# Simulador_Sensor_Hall.net
KiCad netlist of a schematic drawn in EAGLE
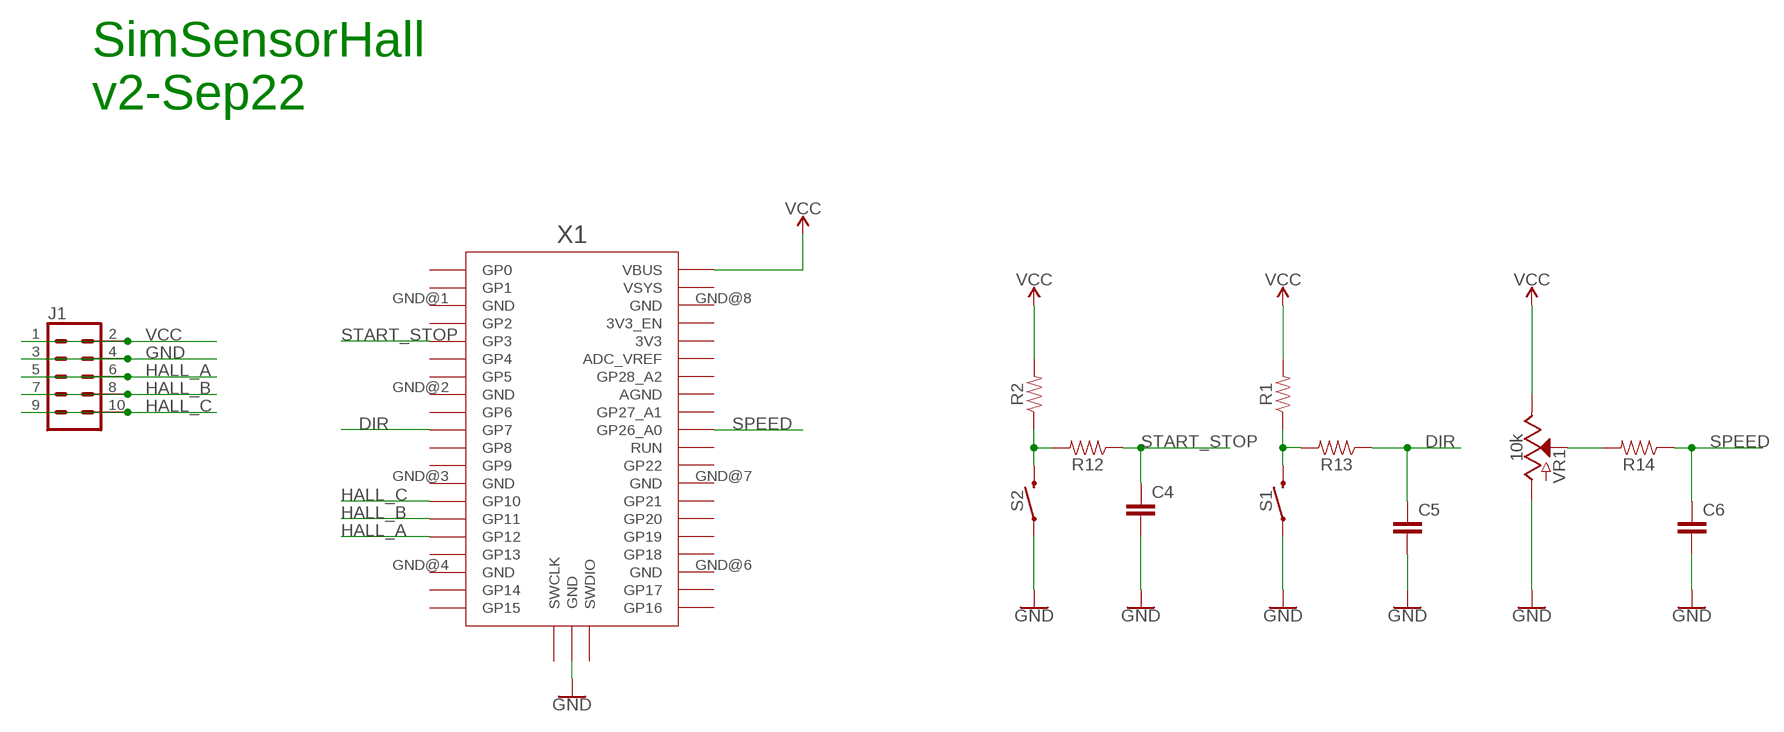
[diagram p0: schematic, sheet 1]

(export (version "E")
  (design (tool "Eeschema 10.0.6"))
  (components
    (comp (ref "C4")
      (value "C-EUC0805K")
      (footprint "eagle-import:C0805K")
      (libsource (lib "eagle-import") (part "C-EUC0805K"))
    )
    (comp (ref "C5")
      (value "C-EUC0805K")
      (footprint "eagle-import:C0805K")
      (libsource (lib "eagle-import") (part "C-EUC0805K"))
    )
    (comp (ref "C6")
      (value "C-EUC0805K")
      (footprint "eagle-import:C0805K")
      (libsource (lib "eagle-import") (part "C-EUC0805K"))
    )
    (comp (ref "J1")
      (value "CONN_05X2PTH")
      (footprint "eagle-import:2X5")
      (libsource (lib "eagle-import") (part "CONN_05X2PTH"))
    )
    (comp (ref "R1")
      (value "RESISTOR0805")
      (footprint "eagle-import:0805")
      (libsource (lib "eagle-import") (part "RESISTOR0805"))
    )
    (comp (ref "R2")
      (value "RESISTOR0805")
      (footprint "eagle-import:0805")
      (libsource (lib "eagle-import") (part "RESISTOR0805"))
    )
    (comp (ref "R12")
      (value "RESISTOR0805")
      (footprint "eagle-import:0805")
      (libsource (lib "eagle-import") (part "RESISTOR0805"))
    )
    (comp (ref "R13")
      (value "RESISTOR0805")
      (footprint "eagle-import:0805")
      (libsource (lib "eagle-import") (part "RESISTOR0805"))
    )
    (comp (ref "R14")
      (value "RESISTOR0805")
      (footprint "eagle-import:0805")
      (libsource (lib "eagle-import") (part "RESISTOR0805"))
    )
    (comp (ref "S1")
      (value "MOMENTARY-SWITCH-SPST-SMD-6.2MM-TALL")
      (footprint "eagle-import:TACTILE_SWITCH_SMD_6.2MM_TALL")
      (libsource (lib "eagle-import") (part "MOMENTARY-SWITCH-SPST-SMD-6.2MM-TALL"))
    )
    (comp (ref "S2")
      (value "MOMENTARY-SWITCH-SPST-SMD-6.2MM-TALL")
      (footprint "eagle-import:TACTILE_SWITCH_SMD_6.2MM_TALL")
      (libsource (lib "eagle-import") (part "MOMENTARY-SWITCH-SPST-SMD-6.2MM-TALL"))
    )
    (comp (ref "VR1")
      (value "10k")
      (footprint "eagle-import:POT-PTH-ALPS")
      (libsource (lib "eagle-import") (part "POTENTIOMETER-PTH-9MM-1/20W-20%"))
    )
    (comp (ref "X1")
      (value "RPI_PICO_IG-TH")
      (footprint "eagle-import:RPI_PICO_TH")
      (libsource (lib "eagle-import") (part "RPI_PICO_IG-TH"))
    )
  )
  (nets
    (net (code "1") (name "/DIR") (class "Default")
      (node (ref "C5") (pin "1") (pinfunction "1_1") (pintype "passive"))
      (node (ref "R13") (pin "1") (pinfunction "1_1") (pintype "passive"))
      (node (ref "X1") (pin "GP7") (pinfunction "GP7_GP7") (pintype "bidirectional"))
    )
    (net (code "2") (name "/HALL_A") (class "Default")
      (node (ref "J1") (pin "5") (pinfunction "5_5") (pintype "passive"))
      (node (ref "J1") (pin "6") (pinfunction "6_6") (pintype "passive"))
      (node (ref "X1") (pin "GP12") (pinfunction "GP12_GP12") (pintype "bidirectional"))
    )
    (net (code "3") (name "/HALL_B") (class "Default")
      (node (ref "J1") (pin "7") (pinfunction "7_7") (pintype "passive"))
      (node (ref "J1") (pin "8") (pinfunction "8_8") (pintype "passive"))
      (node (ref "X1") (pin "GP11") (pinfunction "GP11_GP11") (pintype "bidirectional"))
    )
    (net (code "4") (name "/HALL_C") (class "Default")
      (node (ref "J1") (pin "10") (pinfunction "10_10") (pintype "passive"))
      (node (ref "J1") (pin "9") (pinfunction "9_9") (pintype "passive"))
      (node (ref "X1") (pin "GP10") (pinfunction "GP10_GP10") (pintype "bidirectional"))
    )
    (net (code "5") (name "/SPEED") (class "Default")
      (node (ref "C6") (pin "1") (pinfunction "1_1") (pintype "passive"))
      (node (ref "R14") (pin "1") (pinfunction "1_1") (pintype "passive"))
      (node (ref "X1") (pin "GP26_A0") (pinfunction "GP26_A0_GP26_A0") (pintype "bidirectional"))
    )
    (net (code "6") (name "/START_STOP") (class "Default")
      (node (ref "C4") (pin "1") (pinfunction "1_1") (pintype "passive"))
      (node (ref "R12") (pin "1") (pinfunction "1_1") (pintype "passive"))
      (node (ref "X1") (pin "GP3") (pinfunction "GP3_GP3") (pintype "bidirectional"))
    )
    (net (code "7") (name "GND") (class "Default")
      (node (ref "C4") (pin "2") (pinfunction "2_2") (pintype "passive"))
      (node (ref "C5") (pin "2") (pinfunction "2_2") (pintype "passive"))
      (node (ref "C6") (pin "2") (pinfunction "2_2") (pintype "passive"))
      (node (ref "J1") (pin "3") (pinfunction "3_3") (pintype "passive"))
      (node (ref "J1") (pin "4") (pinfunction "4_4") (pintype "passive"))
      (node (ref "S1") (pin "A2") (pinfunction "1_A2") (pintype "passive"))
      (node (ref "S2") (pin "A2") (pinfunction "1_A2") (pintype "passive"))
      (node (ref "VR1") (pin "P$3") (pinfunction "A_P$3") (pintype "passive"))
      (node (ref "X1") (pin "GND@5") (pinfunction "GND_GND@5") (pintype "bidirectional"))
    )
    (net (code "8") (name "Net-(S1-2)") (class "Default")
      (node (ref "R1") (pin "1") (pinfunction "1_1") (pintype "passive"))
      (node (ref "R13") (pin "2") (pinfunction "2_2") (pintype "passive"))
      (node (ref "S1") (pin "B2") (pinfunction "2_B2") (pintype "passive"))
    )
    (net (code "9") (name "Net-(S2-2)") (class "Default")
      (node (ref "R12") (pin "2") (pinfunction "2_2") (pintype "passive"))
      (node (ref "R2") (pin "1") (pinfunction "1_1") (pintype "passive"))
      (node (ref "S2") (pin "B2") (pinfunction "2_B2") (pintype "passive"))
    )
    (net (code "10") (name "Net-(VR1-S)") (class "Default")
      (node (ref "R14") (pin "2") (pinfunction "2_2") (pintype "passive"))
      (node (ref "VR1") (pin "P$2") (pinfunction "S_P$2") (pintype "passive"))
    )
    (net (code "11") (name "VCC") (class "Default")
      (node (ref "J1") (pin "1") (pinfunction "1_1") (pintype "passive"))
      (node (ref "J1") (pin "2") (pinfunction "2_2") (pintype "passive"))
      (node (ref "R1") (pin "2") (pinfunction "2_2") (pintype "passive"))
      (node (ref "R2") (pin "2") (pinfunction "2_2") (pintype "passive"))
      (node (ref "VR1") (pin "P$1") (pinfunction "E_P$1") (pintype "passive"))
      (node (ref "X1") (pin "VBUS") (pinfunction "VBUS_VBUS") (pintype "bidirectional"))
    )
    (net (code "12") (name "unconnected-(X1-GND-PadGND@1)") (class "Default")
      (node (ref "X1") (pin "GND@1") (pinfunction "GND_GND@1") (pintype "bidirectional"))
    )
    (net (code "13") (name "unconnected-(X1-GND-PadGND@2)") (class "Default")
      (node (ref "X1") (pin "GND@2") (pinfunction "GND_GND@2") (pintype "bidirectional"))
    )
    (net (code "14") (name "unconnected-(X1-GND-PadGND@3)") (class "Default")
      (node (ref "X1") (pin "GND@3") (pinfunction "GND_GND@3") (pintype "bidirectional"))
    )
    (net (code "15") (name "unconnected-(X1-GND-PadGND@4)") (class "Default")
      (node (ref "X1") (pin "GND@4") (pinfunction "GND_GND@4") (pintype "bidirectional"))
    )
    (net (code "16") (name "unconnected-(X1-GND-PadGND@6)") (class "Default")
      (node (ref "X1") (pin "GND@6") (pinfunction "GND_GND@6") (pintype "bidirectional"))
    )
    (net (code "17") (name "unconnected-(X1-GND-PadGND@7)") (class "Default")
      (node (ref "X1") (pin "GND@7") (pinfunction "GND_GND@7") (pintype "bidirectional"))
    )
    (net (code "18") (name "unconnected-(X1-GND-PadGND@8)") (class "Default")
      (node (ref "X1") (pin "GND@8") (pinfunction "GND_GND@8") (pintype "bidirectional"))
    )
    (net (code "19") (name "unconnected-(X1-Pad3V3)") (class "Default")
      (node (ref "X1") (pin "3V3") (pinfunction "3V3_3V3") (pintype "bidirectional"))
    )
    (net (code "20") (name "unconnected-(X1-Pad3V3_EN)") (class "Default")
      (node (ref "X1") (pin "3V3_EN") (pinfunction "3V3_EN_3V3_EN") (pintype "bidirectional"))
    )
    (net (code "21") (name "unconnected-(X1-PadADC_VREF)") (class "Default")
      (node (ref "X1") (pin "ADC_VREF") (pinfunction "ADC_VREF_ADC_VREF") (pintype "bidirectional"))
    )
    (net (code "22") (name "unconnected-(X1-PadAGND)") (class "Default")
      (node (ref "X1") (pin "AGND") (pinfunction "AGND_AGND") (pintype "bidirectional"))
    )
    (net (code "23") (name "unconnected-(X1-PadGP0)") (class "Default")
      (node (ref "X1") (pin "GP0") (pinfunction "GP0_GP0") (pintype "bidirectional"))
    )
    (net (code "24") (name "unconnected-(X1-PadGP1)") (class "Default")
      (node (ref "X1") (pin "GP1") (pinfunction "GP1_GP1") (pintype "bidirectional"))
    )
    (net (code "25") (name "unconnected-(X1-PadGP2)") (class "Default")
      (node (ref "X1") (pin "GP2") (pinfunction "GP2_GP2") (pintype "bidirectional"))
    )
    (net (code "26") (name "unconnected-(X1-PadGP4)") (class "Default")
      (node (ref "X1") (pin "GP4") (pinfunction "GP4_GP4") (pintype "bidirectional"))
    )
    (net (code "27") (name "unconnected-(X1-PadGP5)") (class "Default")
      (node (ref "X1") (pin "GP5") (pinfunction "GP5_GP5") (pintype "bidirectional"))
    )
    (net (code "28") (name "unconnected-(X1-PadGP6)") (class "Default")
      (node (ref "X1") (pin "GP6") (pinfunction "GP6_GP6") (pintype "bidirectional"))
    )
    (net (code "29") (name "unconnected-(X1-PadGP8)") (class "Default")
      (node (ref "X1") (pin "GP8") (pinfunction "GP8_GP8") (pintype "bidirectional"))
    )
    (net (code "30") (name "unconnected-(X1-PadGP9)") (class "Default")
      (node (ref "X1") (pin "GP9") (pinfunction "GP9_GP9") (pintype "bidirectional"))
    )
    (net (code "31") (name "unconnected-(X1-PadGP13)") (class "Default")
      (node (ref "X1") (pin "GP13") (pinfunction "GP13_GP13") (pintype "bidirectional"))
    )
    (net (code "32") (name "unconnected-(X1-PadGP14)") (class "Default")
      (node (ref "X1") (pin "GP14") (pinfunction "GP14_GP14") (pintype "bidirectional"))
    )
    (net (code "33") (name "unconnected-(X1-PadGP15)") (class "Default")
      (node (ref "X1") (pin "GP15") (pinfunction "GP15_GP15") (pintype "bidirectional"))
    )
    (net (code "34") (name "unconnected-(X1-PadGP16)") (class "Default")
      (node (ref "X1") (pin "GP16") (pinfunction "GP16_GP16") (pintype "bidirectional"))
    )
    (net (code "35") (name "unconnected-(X1-PadGP17)") (class "Default")
      (node (ref "X1") (pin "GP17") (pinfunction "GP17_GP17") (pintype "bidirectional"))
    )
    (net (code "36") (name "unconnected-(X1-PadGP18)") (class "Default")
      (node (ref "X1") (pin "GP18") (pinfunction "GP18_GP18") (pintype "bidirectional"))
    )
    (net (code "37") (name "unconnected-(X1-PadGP19)") (class "Default")
      (node (ref "X1") (pin "GP19") (pinfunction "GP19_GP19") (pintype "bidirectional"))
    )
    (net (code "38") (name "unconnected-(X1-PadGP20)") (class "Default")
      (node (ref "X1") (pin "GP20") (pinfunction "GP20_GP20") (pintype "bidirectional"))
    )
    (net (code "39") (name "unconnected-(X1-PadGP21)") (class "Default")
      (node (ref "X1") (pin "GP21") (pinfunction "GP21_GP21") (pintype "bidirectional"))
    )
    (net (code "40") (name "unconnected-(X1-PadGP22)") (class "Default")
      (node (ref "X1") (pin "GP22") (pinfunction "GP22_GP22") (pintype "bidirectional"))
    )
    (net (code "41") (name "unconnected-(X1-PadGP27_A1)") (class "Default")
      (node (ref "X1") (pin "GP27_A1") (pinfunction "GP27_A1_GP27_A1") (pintype "bidirectional"))
    )
    (net (code "42") (name "unconnected-(X1-PadGP28_A2)") (class "Default")
      (node (ref "X1") (pin "GP28_A2") (pinfunction "GP28_A2_GP28_A2") (pintype "bidirectional"))
    )
    (net (code "43") (name "unconnected-(X1-PadRUN)") (class "Default")
      (node (ref "X1") (pin "RUN") (pinfunction "RUN_RUN") (pintype "bidirectional"))
    )
    (net (code "44") (name "unconnected-(X1-PadSWCLK)") (class "Default")
      (node (ref "X1") (pin "SWCLK") (pinfunction "SWCLK_SWCLK") (pintype "bidirectional"))
    )
    (net (code "45") (name "unconnected-(X1-PadSWDIO)") (class "Default")
      (node (ref "X1") (pin "SWDIO") (pinfunction "SWDIO_SWDIO") (pintype "bidirectional"))
    )
    (net (code "46") (name "unconnected-(X1-PadVSYS)") (class "Default")
      (node (ref "X1") (pin "VSYS") (pinfunction "VSYS_VSYS") (pintype "bidirectional"))
    )
  )
)
